# Camera.net
KiCad netlist of a schematic drawn in Altium Designer
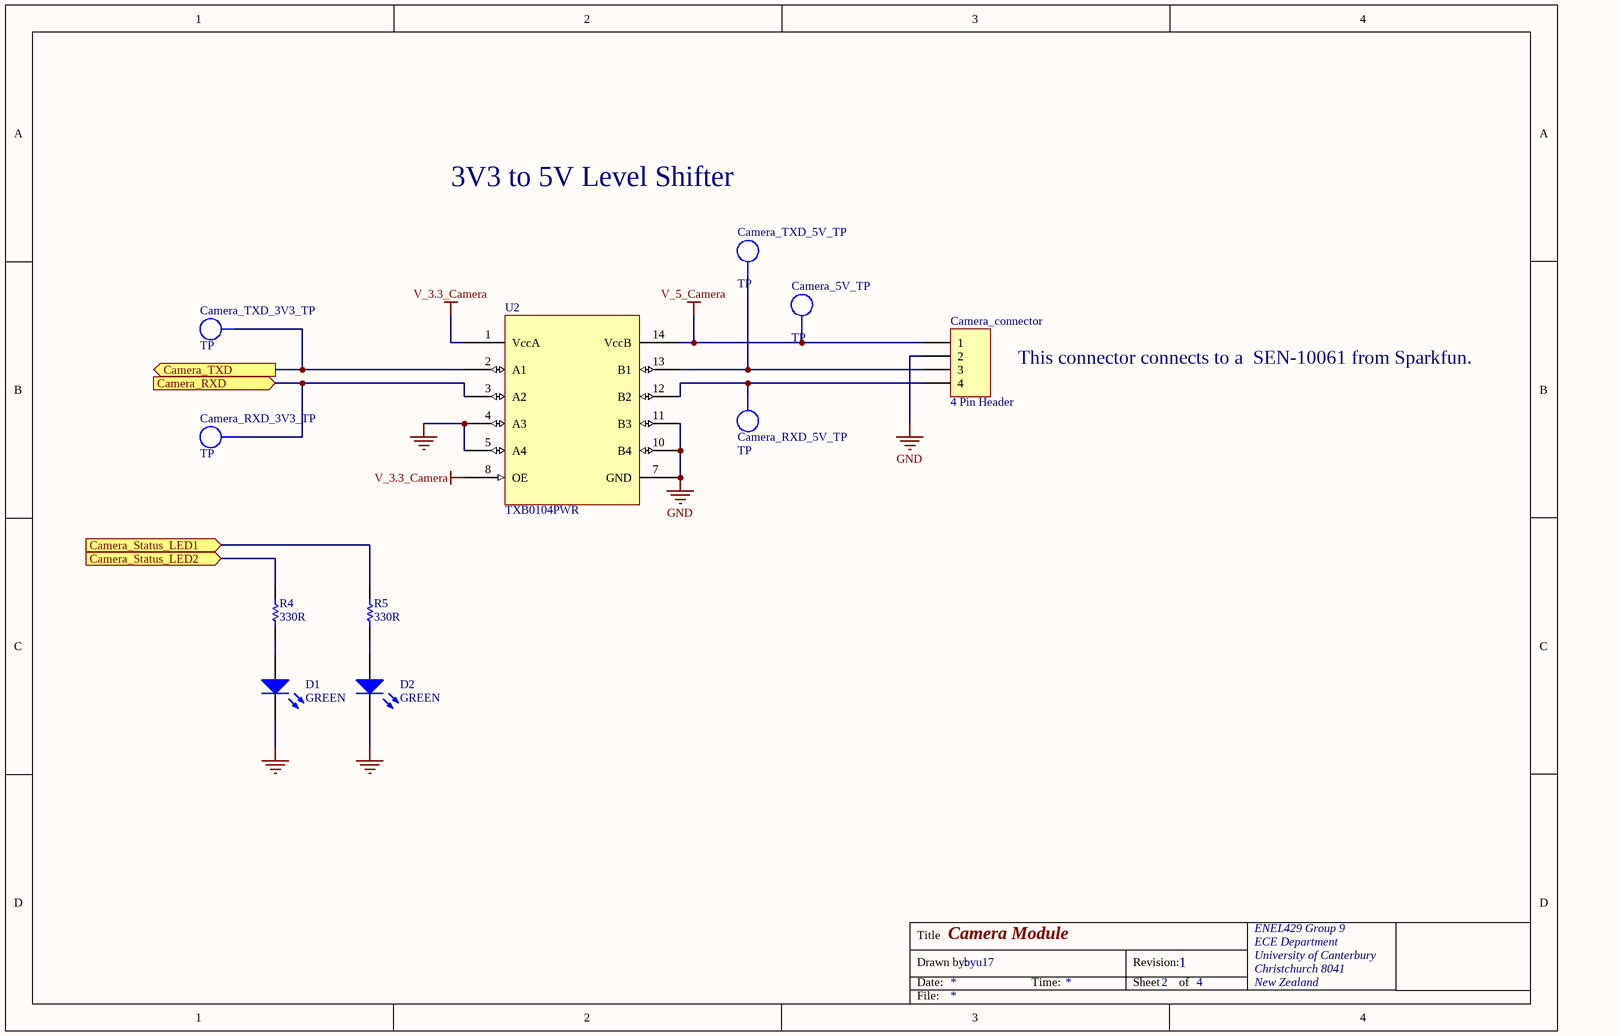
[diagram p0: Camera.SchDoc]

(export (version "E")
  (design (tool "Eeschema 10.0.6"))
  (components
    (comp (ref "Camera_5V_TP")
      (value "TP")
      (footprint "TEST_POINT_4X2MM")
      (description "Test-Point")
      (fields (field (name "PART NUMBER") "TP_TESTPOINT"))
      (libsource (lib "ENEL429_4") (part "TP_TESTPOINT"))
    )
    (comp (ref "Camera_connector")
      (value "4 Pin Header")
      (footprint "CONN_4X1_SMT_RA_1.25MM")
      (description "CONN HDR VERT 4POS .100\" SNGL")
      (fields (field (name "MANUFACTURER") "Molex") (field (name "PART NUMBER") "JP_4PIN HDR_SMT_RA_MOLEX_1"))
      (libsource (lib "ENEL429_4") (part "JP_4PIN HDR_SMT_RA_MOLEX_1"))
    )
    (comp (ref "Camera_RXD_3V3_TP")
      (value "TP")
      (footprint "TEST_POINT_4X2MM")
      (description "Test-Point")
      (fields (field (name "PART NUMBER") "TP_TESTPOINT"))
      (libsource (lib "ENEL429_4") (part "TP_TESTPOINT"))
    )
    (comp (ref "Camera_RXD_5V_TP")
      (value "TP")
      (footprint "TEST_POINT_4X2MM")
      (description "Test-Point")
      (fields (field (name "PART NUMBER") "TP_TESTPOINT"))
      (libsource (lib "ENEL429_4") (part "TP_TESTPOINT"))
    )
    (comp (ref "Camera_TXD_3V3_TP")
      (value "TP")
      (footprint "TEST_POINT_4X2MM")
      (description "Test-Point")
      (fields (field (name "PART NUMBER") "TP_TESTPOINT"))
      (libsource (lib "ENEL429_4") (part "TP_TESTPOINT"))
    )
    (comp (ref "Camera_TXD_5V_TP")
      (value "TP")
      (footprint "TEST_POINT_4X2MM")
      (description "Test-Point")
      (fields (field (name "PART NUMBER") "TP_TESTPOINT"))
      (libsource (lib "ENEL429_4") (part "TP_TESTPOINT"))
    )
    (comp (ref "D1")
      (value "GREEN")
      (footprint "DIODE_0805")
      (description "Green LED 0805")
      (fields (field (name "PART NUMBER") "DL_LED Green 0805") (field (name "MANUFACTURER") "Vishay"))
      (libsource (lib "ENEL429_4") (part "DL_LED Green 0805"))
    )
    (comp (ref "D2")
      (value "GREEN")
      (footprint "DIODE_0805")
      (description "Green LED 0805")
      (fields (field (name "PART NUMBER") "DL_LED Green 0805") (field (name "MANUFACTURER") "Vishay"))
      (libsource (lib "ENEL429_4") (part "DL_LED Green 0805"))
    )
    (comp (ref "R4")
      (value "330R")
      (footprint "0603")
      (description "RES 330 OHM 1/10W 1% 0603 SMD")
      (fields (field (name "PART NUMBER") "RS_330R 0603") (field (name "MANUFACTURER") "Yageo"))
      (libsource (lib "ENEL429_4") (part "RS_330R 0603"))
    )
    (comp (ref "R5")
      (value "330R")
      (footprint "0603")
      (description "RES 330 OHM 1/10W 1% 0603 SMD")
      (fields (field (name "PART NUMBER") "RS_330R 0603") (field (name "MANUFACTURER") "Yageo"))
      (libsource (lib "ENEL429_4") (part "RS_330R 0603"))
    )
    (comp (ref "U2")
      (value "TXB0104PWR")
      (footprint "TSSOP-14_PW")
      (description "IC VOLT-LEVEL TRANSLATOR 14TSSOP")
      (fields (field (name "MANUFACTURER") "Texas Instruments") (field (name "PART NUMBER") "IC_TXB0104PWR"))
      (libsource (lib "ENEL429_4") (part "IC_TXB0104PWR"))
    )
  )
  (nets
    (net (code "1") (name "/Camera_RXD") (class "Default")
      (node (ref "Camera_RXD_3V3_TP") (pin "1") (pinfunction "1_1") (pintype "passive"))
      (node (ref "U2") (pin "3") (pinfunction "A2_3") (pintype "bidirectional"))
    )
    (net (code "2") (name "/Camera_Status_LED1") (class "Default")
      (node (ref "R5") (pin "1") (pinfunction "1_1") (pintype "passive"))
    )
    (net (code "3") (name "/Camera_Status_LED2") (class "Default")
      (node (ref "R4") (pin "1") (pinfunction "1_1") (pintype "passive"))
    )
    (net (code "4") (name "/Camera_TXD") (class "Default")
      (node (ref "Camera_TXD_3V3_TP") (pin "1") (pinfunction "1_1") (pintype "passive"))
      (node (ref "U2") (pin "2") (pinfunction "A1_2") (pintype "bidirectional"))
    )
    (net (code "5") (name "GND") (class "Default")
      (node (ref "Camera_connector") (pin "2") (pinfunction "2_2") (pintype "passive"))
      (node (ref "D1") (pin "2") (pinfunction "K_2") (pintype "passive"))
      (node (ref "D2") (pin "2") (pinfunction "K_2") (pintype "passive"))
      (node (ref "U2") (pin "10") (pinfunction "B4_10") (pintype "bidirectional"))
      (node (ref "U2") (pin "11") (pinfunction "B3_11") (pintype "bidirectional"))
      (node (ref "U2") (pin "4") (pinfunction "A3_4") (pintype "bidirectional"))
      (node (ref "U2") (pin "5") (pinfunction "A4_5") (pintype "bidirectional"))
      (node (ref "U2") (pin "7") (pinfunction "GND_7") (pintype "power_in"))
    )
    (net (code "6") (name "Net-(D1-A)") (class "Default")
      (node (ref "D1") (pin "1") (pinfunction "A_1") (pintype "passive"))
      (node (ref "R4") (pin "2") (pinfunction "2_2") (pintype "passive"))
    )
    (net (code "7") (name "Net-(D2-A)") (class "Default")
      (node (ref "D2") (pin "1") (pinfunction "A_1") (pintype "passive"))
      (node (ref "R5") (pin "2") (pinfunction "2_2") (pintype "passive"))
    )
    (net (code "8") (name "Net-(U2-B1)") (class "Default")
      (node (ref "Camera_TXD_5V_TP") (pin "1") (pinfunction "1_1") (pintype "passive"))
      (node (ref "Camera_connector") (pin "3") (pinfunction "3_3") (pintype "passive"))
      (node (ref "U2") (pin "13") (pinfunction "B1_13") (pintype "bidirectional"))
    )
    (net (code "9") (name "Net-(U2-B2)") (class "Default")
      (node (ref "Camera_RXD_5V_TP") (pin "1") (pinfunction "1_1") (pintype "passive"))
      (node (ref "Camera_connector") (pin "4") (pinfunction "4_4") (pintype "passive"))
      (node (ref "U2") (pin "12") (pinfunction "B2_12") (pintype "bidirectional"))
    )
    (net (code "10") (name "V_3.3_Camera") (class "Default")
      (node (ref "U2") (pin "1") (pinfunction "VccA_1") (pintype "power_in"))
      (node (ref "U2") (pin "8") (pinfunction "OE_8") (pintype "input"))
    )
    (net (code "11") (name "V_5_Camera") (class "Default")
      (node (ref "Camera_5V_TP") (pin "1") (pinfunction "1_1") (pintype "passive"))
      (node (ref "Camera_connector") (pin "1") (pinfunction "1_1") (pintype "passive"))
      (node (ref "U2") (pin "14") (pinfunction "VccB_14") (pintype "power_in"))
    )
  )
)
